# Peripherals.net
KiCad netlist of a schematic drawn in Altium Designer
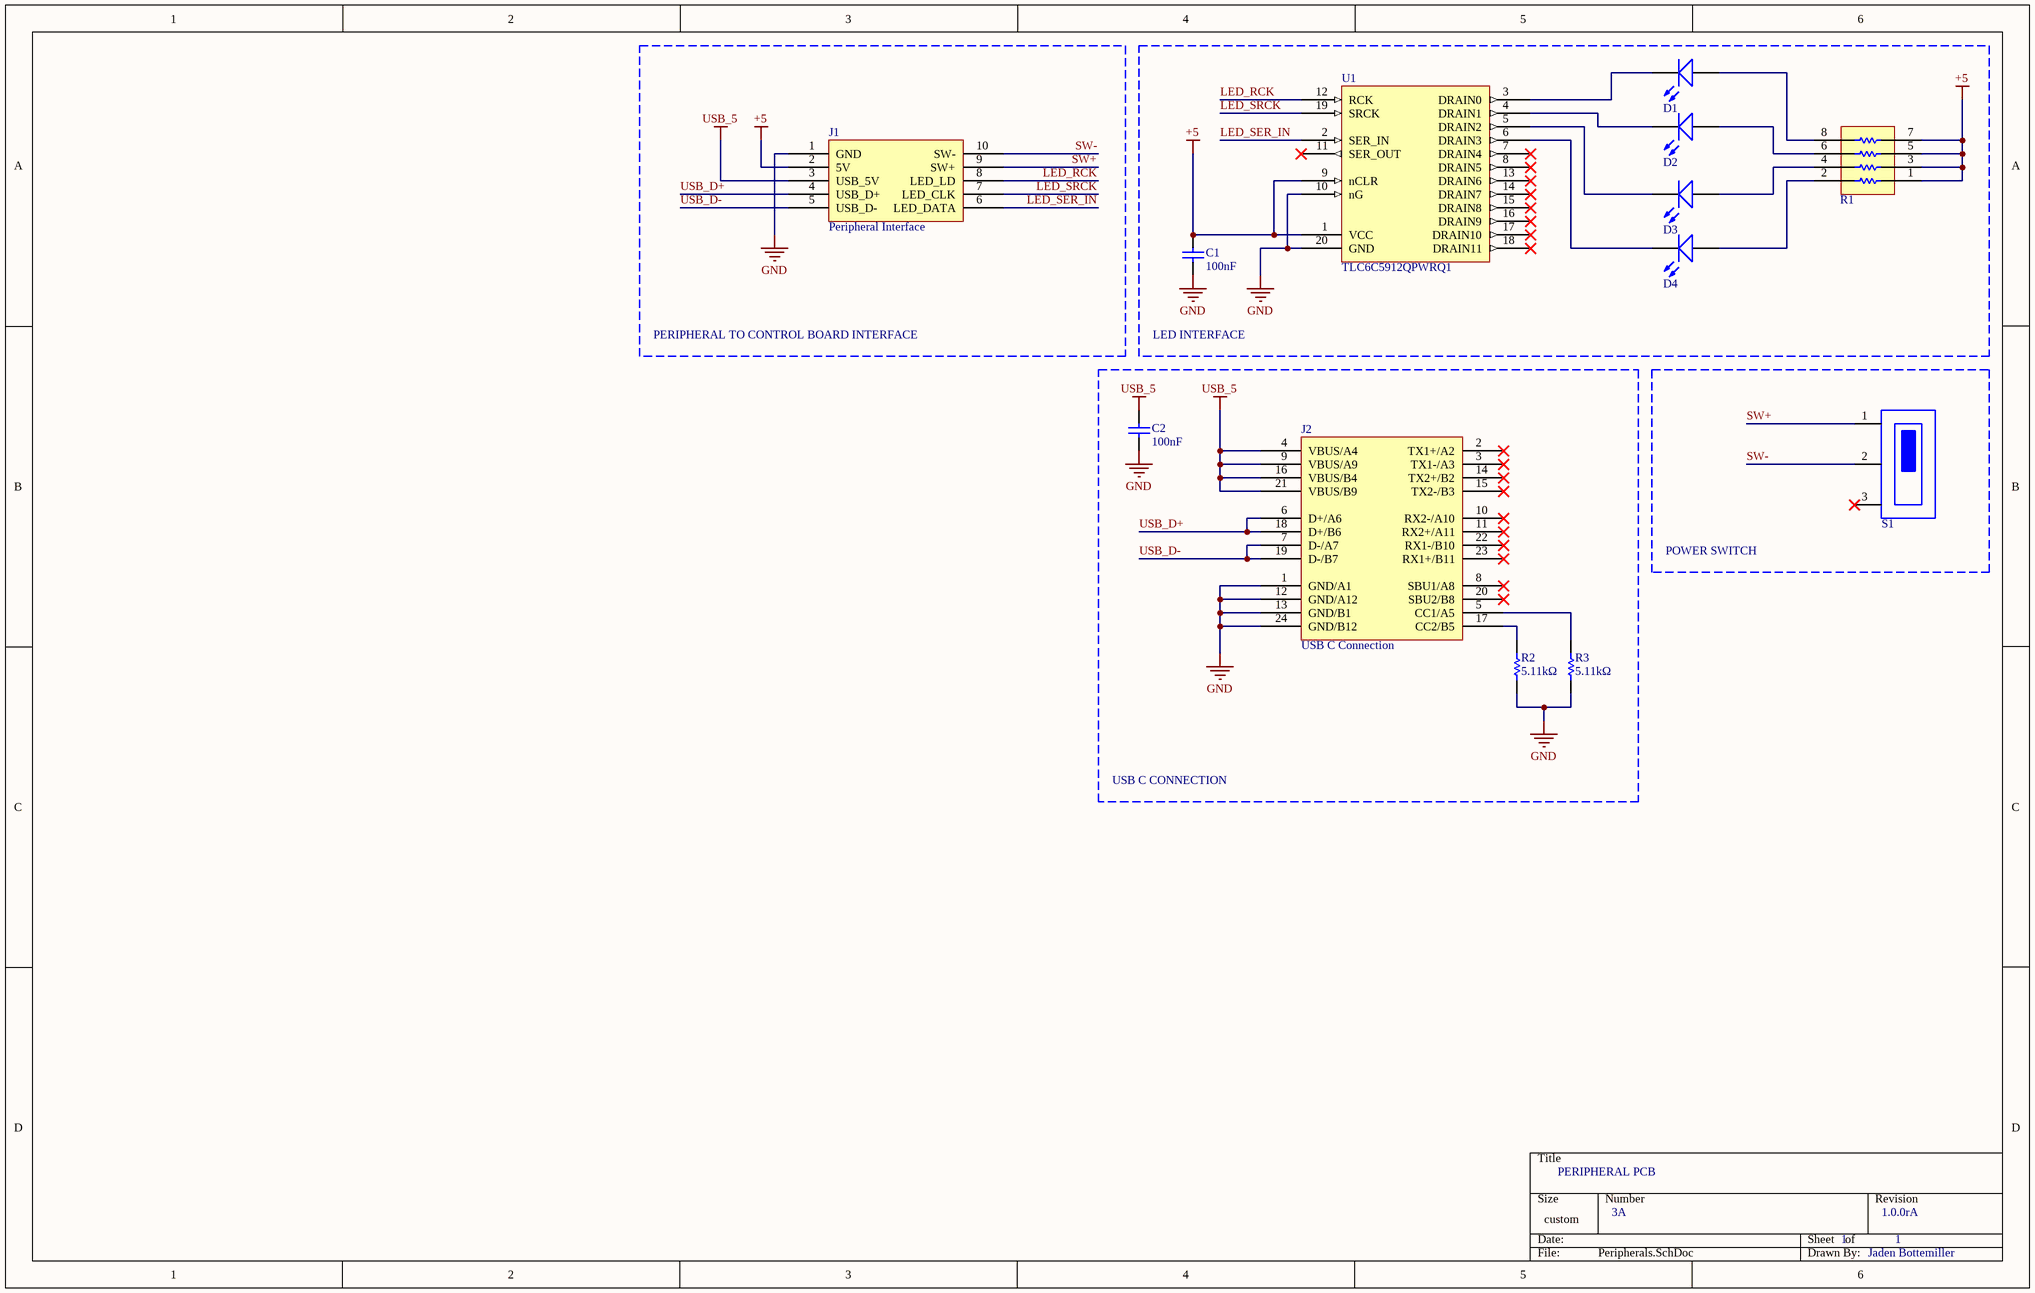
[diagram p0: Peripherals.SchDoc]

(export (version "E")
  (design (tool "Eeschema 10.0.6"))
  (components
    (comp (ref "C1")
      (value "100nF")
      (description "Standard Capacitor")
      (fields (field (name "Comment") "CAP"))
      (libsource (lib "NikoboticsLib") (part "CAP"))
    )
    (comp (ref "C2")
      (value "100nF")
      (description "Standard Capacitor")
      (fields (field (name "Comment") "CAP"))
      (libsource (lib "NikoboticsLib") (part "CAP"))
    )
    (comp (ref "D1")
      (value "LED")
      (description "Standard LED")
      (libsource (lib "NikoboticsLib") (part "LED"))
    )
    (comp (ref "D2")
      (value "LED")
      (description "Standard LED")
      (libsource (lib "NikoboticsLib") (part "LED"))
    )
    (comp (ref "D3")
      (value "LED")
      (description "Standard LED")
      (libsource (lib "NikoboticsLib") (part "LED"))
    )
    (comp (ref "D4")
      (value "LED")
      (description "Standard LED")
      (libsource (lib "NikoboticsLib") (part "LED"))
    )
    (comp (ref "J1")
      (value "Peripheral Interface")
      (description "Interface between peripheral board and control board.")
      (libsource (lib "NikoboticsLib") (part "PERIPHERAL_INTERFACE"))
    )
    (comp (ref "J2")
      (value "USB C Connection")
      (description "Standard USBC Connection")
      (libsource (lib "NikoboticsLib") (part "USBC_CONN"))
    )
    (comp (ref "R1")
      (value "RESNET")
      (description "Standard Resistor Network with 4 Resistors")
      (libsource (lib "NikoboticsLib") (part "RESNET4"))
    )
    (comp (ref "R2")
      (value "5.11kΩ")
      (description "Standard Resistor")
      (fields (field (name "Comment") "RES"))
      (libsource (lib "NikoboticsLib") (part "RES"))
    )
    (comp (ref "R3")
      (value "5.11kΩ")
      (description "Standard Resistor")
      (fields (field (name "Comment") "RES"))
      (libsource (lib "NikoboticsLib") (part "RES"))
    )
    (comp (ref "S1")
      (value "SPDT_SW")
      (description "Standard Single-Pole Double-Throw Switch. Check pinning before assigning footprint.")
      (libsource (lib "NikoboticsLib") (part "SPDT_SW"))
    )
    (comp (ref "U1")
      (value "TLC6C5912QPWRQ1")
      (description "LED Driver IC 12 Output Linear Shift Register 50mA")
      (libsource (lib "NikoboticsLib") (part "TLC6C5912QPWRQ1"))
    )
  )
  (nets
    (net (code "1") (name "+5") (class "Default")
      (node (ref "C1") (pin "2") (pinfunction "2_2") (pintype "passive"))
      (node (ref "J1") (pin "2") (pinfunction "5V_2") (pintype "passive"))
      (node (ref "R1") (pin "1") (pinfunction "Pin_1") (pintype "passive"))
      (node (ref "R1") (pin "3") (pinfunction "Pin_3") (pintype "passive"))
      (node (ref "R1") (pin "5") (pinfunction "Pin_5") (pintype "passive"))
      (node (ref "R1") (pin "7") (pinfunction "Pin_7") (pintype "passive"))
      (node (ref "U1") (pin "1") (pinfunction "VCC_1") (pintype "power_in"))
      (node (ref "U1") (pin "9") (pinfunction "nCLR_9") (pintype "input"))
    )
    (net (code "2") (name "/LED_RCK") (class "Default")
      (node (ref "J1") (pin "8") (pinfunction "LED_LD_8") (pintype "passive"))
      (node (ref "U1") (pin "12") (pinfunction "RCK_12") (pintype "input"))
    )
    (net (code "3") (name "/LED_SER_IN") (class "Default")
      (node (ref "J1") (pin "6") (pinfunction "LED_DATA_6") (pintype "passive"))
      (node (ref "U1") (pin "2") (pinfunction "SER_IN_2") (pintype "input"))
    )
    (net (code "4") (name "/LED_SRCK") (class "Default")
      (node (ref "J1") (pin "7") (pinfunction "LED_CLK_7") (pintype "passive"))
      (node (ref "U1") (pin "19") (pinfunction "SRCK_19") (pintype "input"))
    )
    (net (code "5") (name "/SW+") (class "Default")
      (node (ref "J1") (pin "9") (pinfunction "SW+_9") (pintype "passive"))
      (node (ref "S1") (pin "1") (pinfunction "Pin_1") (pintype "passive"))
    )
    (net (code "6") (name "/SW-") (class "Default")
      (node (ref "J1") (pin "10") (pinfunction "SW-_10") (pintype "passive"))
      (node (ref "S1") (pin "2") (pinfunction "Pin_2") (pintype "passive"))
    )
    (net (code "7") (name "/USB_D+") (class "Default")
      (node (ref "J1") (pin "4") (pinfunction "USB_D+_4") (pintype "passive"))
      (node (ref "J2") (pin "18") (pinfunction "D+/B6_18") (pintype "passive"))
      (node (ref "J2") (pin "6") (pinfunction "D+/A6_6") (pintype "passive"))
    )
    (net (code "8") (name "/USB_D-") (class "Default")
      (node (ref "J1") (pin "5") (pinfunction "USB_D-_5") (pintype "passive"))
      (node (ref "J2") (pin "19") (pinfunction "D-/B7_19") (pintype "passive"))
      (node (ref "J2") (pin "7") (pinfunction "D-/A7_7") (pintype "passive"))
    )
    (net (code "9") (name "GND") (class "Default")
      (node (ref "C1") (pin "1") (pinfunction "1_1") (pintype "passive"))
      (node (ref "C2") (pin "1") (pinfunction "1_1") (pintype "passive"))
      (node (ref "J1") (pin "1") (pinfunction "GND_1") (pintype "passive"))
      (node (ref "J2") (pin "1") (pinfunction "GND/A1_1") (pintype "passive"))
      (node (ref "J2") (pin "12") (pinfunction "GND/A12_12") (pintype "passive"))
      (node (ref "J2") (pin "13") (pinfunction "GND/B1_13") (pintype "passive"))
      (node (ref "J2") (pin "24") (pinfunction "GND/B12_24") (pintype "passive"))
      (node (ref "R2") (pin "1") (pinfunction "1_1") (pintype "passive"))
      (node (ref "R3") (pin "1") (pinfunction "1_1") (pintype "passive"))
      (node (ref "U1") (pin "10") (pinfunction "nG_10") (pintype "input"))
      (node (ref "U1") (pin "20") (pinfunction "GND_20") (pintype "power_in"))
    )
    (net (code "10") (name "Net-(D1-A)") (class "Default")
      (node (ref "D1") (pin "2") (pinfunction "A_2") (pintype "passive"))
      (node (ref "R1") (pin "8") (pinfunction "Pin_8") (pintype "passive"))
    )
    (net (code "11") (name "Net-(D1-K)") (class "Default")
      (node (ref "D1") (pin "1") (pinfunction "K_1") (pintype "passive"))
      (node (ref "U1") (pin "3") (pinfunction "DRAIN0_3") (pintype "output"))
    )
    (net (code "12") (name "Net-(D2-A)") (class "Default")
      (node (ref "D2") (pin "2") (pinfunction "A_2") (pintype "passive"))
      (node (ref "R1") (pin "6") (pinfunction "Pin_6") (pintype "passive"))
    )
    (net (code "13") (name "Net-(D2-K)") (class "Default")
      (node (ref "D2") (pin "1") (pinfunction "K_1") (pintype "passive"))
      (node (ref "U1") (pin "4") (pinfunction "DRAIN1_4") (pintype "output"))
    )
    (net (code "14") (name "Net-(D3-A)") (class "Default")
      (node (ref "D3") (pin "2") (pinfunction "A_2") (pintype "passive"))
      (node (ref "R1") (pin "4") (pinfunction "Pin_4") (pintype "passive"))
    )
    (net (code "15") (name "Net-(D3-K)") (class "Default")
      (node (ref "D3") (pin "1") (pinfunction "K_1") (pintype "passive"))
      (node (ref "U1") (pin "5") (pinfunction "DRAIN2_5") (pintype "output"))
    )
    (net (code "16") (name "Net-(D4-A)") (class "Default")
      (node (ref "D4") (pin "2") (pinfunction "A_2") (pintype "passive"))
      (node (ref "R1") (pin "2") (pinfunction "Pin_2") (pintype "passive"))
    )
    (net (code "17") (name "Net-(D4-K)") (class "Default")
      (node (ref "D4") (pin "1") (pinfunction "K_1") (pintype "passive"))
      (node (ref "U1") (pin "6") (pinfunction "DRAIN3_6") (pintype "output"))
    )
    (net (code "18") (name "Net-(J2-CC1{slash}A5)") (class "Default")
      (node (ref "J2") (pin "5") (pinfunction "CC1/A5_5") (pintype "passive"))
      (node (ref "R3") (pin "2") (pinfunction "2_2") (pintype "passive"))
    )
    (net (code "19") (name "Net-(J2-CC2{slash}B5)") (class "Default")
      (node (ref "J2") (pin "17") (pinfunction "CC2/B5_17") (pintype "passive"))
      (node (ref "R2") (pin "2") (pinfunction "2_2") (pintype "passive"))
    )
    (net (code "20") (name "USB_5") (class "Default")
      (node (ref "C2") (pin "2") (pinfunction "2_2") (pintype "passive"))
      (node (ref "J1") (pin "3") (pinfunction "USB_5V_3") (pintype "passive"))
      (node (ref "J2") (pin "16") (pinfunction "VBUS/B4_16") (pintype "passive"))
      (node (ref "J2") (pin "21") (pinfunction "VBUS/B9_21") (pintype "passive"))
      (node (ref "J2") (pin "4") (pinfunction "VBUS/A4_4") (pintype "passive"))
      (node (ref "J2") (pin "9") (pinfunction "VBUS/A9_9") (pintype "passive"))
    )
    (net (code "21") (name "unconnected-(J2-RX1+{slash}B11-Pad23)") (class "Default")
      (node (ref "J2") (pin "23") (pinfunction "RX1+/B11_23") (pintype "passive+no_connect"))
    )
    (net (code "22") (name "unconnected-(J2-RX1-{slash}B10-Pad22)") (class "Default")
      (node (ref "J2") (pin "22") (pinfunction "RX1-/B10_22") (pintype "passive+no_connect"))
    )
    (net (code "23") (name "unconnected-(J2-RX2+{slash}A11-Pad11)") (class "Default")
      (node (ref "J2") (pin "11") (pinfunction "RX2+/A11_11") (pintype "passive+no_connect"))
    )
    (net (code "24") (name "unconnected-(J2-RX2-{slash}A10-Pad10)") (class "Default")
      (node (ref "J2") (pin "10") (pinfunction "RX2-/A10_10") (pintype "passive+no_connect"))
    )
    (net (code "25") (name "unconnected-(J2-SBU1{slash}A8-Pad8)") (class "Default")
      (node (ref "J2") (pin "8") (pinfunction "SBU1/A8_8") (pintype "passive+no_connect"))
    )
    (net (code "26") (name "unconnected-(J2-SBU2{slash}B8-Pad20)") (class "Default")
      (node (ref "J2") (pin "20") (pinfunction "SBU2/B8_20") (pintype "passive+no_connect"))
    )
    (net (code "27") (name "unconnected-(J2-TX1+{slash}A2-Pad2)") (class "Default")
      (node (ref "J2") (pin "2") (pinfunction "TX1+/A2_2") (pintype "passive+no_connect"))
    )
    (net (code "28") (name "unconnected-(J2-TX1-{slash}A3-Pad3)") (class "Default")
      (node (ref "J2") (pin "3") (pinfunction "TX1-/A3_3") (pintype "passive+no_connect"))
    )
    (net (code "29") (name "unconnected-(J2-TX2+{slash}B2-Pad14)") (class "Default")
      (node (ref "J2") (pin "14") (pinfunction "TX2+/B2_14") (pintype "passive+no_connect"))
    )
    (net (code "30") (name "unconnected-(J2-TX2-{slash}B3-Pad15)") (class "Default")
      (node (ref "J2") (pin "15") (pinfunction "TX2-/B3_15") (pintype "passive+no_connect"))
    )
    (net (code "31") (name "unconnected-(S1-Pin-Pad3)") (class "Default")
      (node (ref "S1") (pin "3") (pinfunction "Pin_3") (pintype "passive+no_connect"))
    )
    (net (code "32") (name "unconnected-(U1-DRAIN4-Pad7)") (class "Default")
      (node (ref "U1") (pin "7") (pinfunction "DRAIN4_7") (pintype "output+no_connect"))
    )
    (net (code "33") (name "unconnected-(U1-DRAIN5-Pad8)") (class "Default")
      (node (ref "U1") (pin "8") (pinfunction "DRAIN5_8") (pintype "output+no_connect"))
    )
    (net (code "34") (name "unconnected-(U1-DRAIN6-Pad13)") (class "Default")
      (node (ref "U1") (pin "13") (pinfunction "DRAIN6_13") (pintype "output+no_connect"))
    )
    (net (code "35") (name "unconnected-(U1-DRAIN7-Pad14)") (class "Default")
      (node (ref "U1") (pin "14") (pinfunction "DRAIN7_14") (pintype "output+no_connect"))
    )
    (net (code "36") (name "unconnected-(U1-DRAIN8-Pad15)") (class "Default")
      (node (ref "U1") (pin "15") (pinfunction "DRAIN8_15") (pintype "output+no_connect"))
    )
    (net (code "37") (name "unconnected-(U1-DRAIN9-Pad16)") (class "Default")
      (node (ref "U1") (pin "16") (pinfunction "DRAIN9_16") (pintype "output+no_connect"))
    )
    (net (code "38") (name "unconnected-(U1-DRAIN10-Pad17)") (class "Default")
      (node (ref "U1") (pin "17") (pinfunction "DRAIN10_17") (pintype "output+no_connect"))
    )
    (net (code "39") (name "unconnected-(U1-DRAIN11-Pad18)") (class "Default")
      (node (ref "U1") (pin "18") (pinfunction "DRAIN11_18") (pintype "output+no_connect"))
    )
    (net (code "40") (name "unconnected-(U1-SER_OUT-Pad11)") (class "Default")
      (node (ref "U1") (pin "11") (pinfunction "SER_OUT_11") (pintype "output+no_connect"))
    )
  )
)
